# ElderBot.net
KiCad netlist of a schematic drawn in Altium Designer
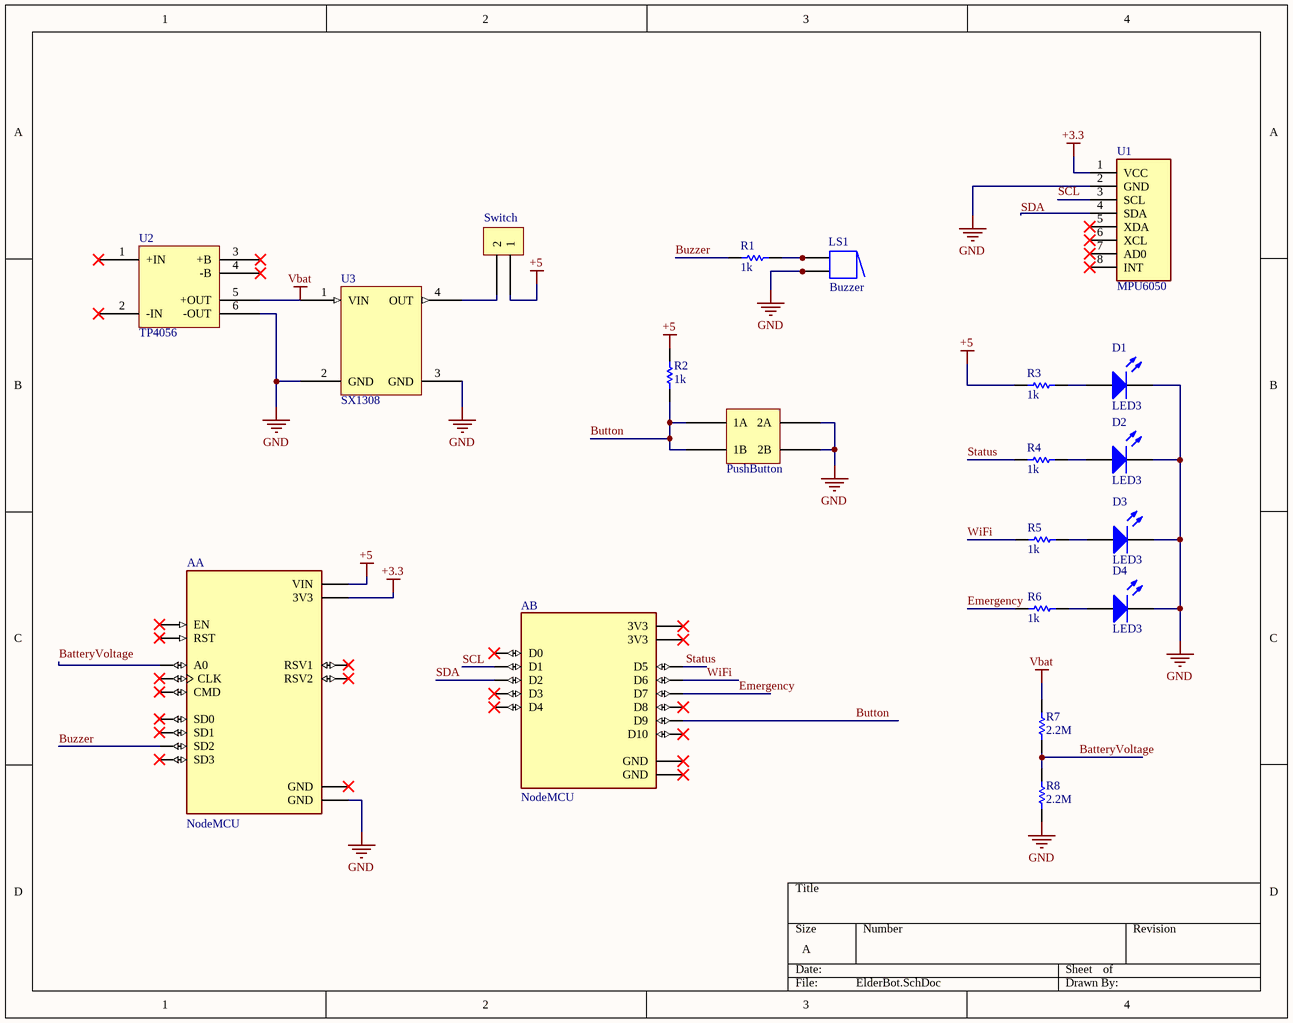
[diagram p0: ElderBot.SchDoc]

(export (version "E")
  (design (tool "Eeschema 10.0.6"))
  (components
    (comp (ref "A")
      (value "NodeMCU")
      (footprint "SEEED_113990105")
      (fields (field (name "MP") "NodeMCU v2") (field (name "MF") "Seeed Technology"))
      (libsource (lib "NodeMCU") (part "113990105"))
    )
    (comp (ref "D1")
      (value "LED3")
      (footprint "3.2X1.6X1.1")
      (description "Typical BLUE SiC LED")
      (fields (field (name "PUBLISHER") "Altium Limited"))
      (libsource (lib "Miscellaneous Devices") (part "LED3"))
    )
    (comp (ref "D2")
      (value "LED3")
      (footprint "3.2X1.6X1.1")
      (description "Typical BLUE SiC LED")
      (fields (field (name "PUBLISHER") "Altium Limited"))
      (libsource (lib "Miscellaneous Devices") (part "LED3"))
    )
    (comp (ref "D3")
      (value "LED3")
      (footprint "3.2X1.6X1.1")
      (description "Typical BLUE SiC LED")
      (fields (field (name "PUBLISHER") "Altium Limited"))
      (libsource (lib "Miscellaneous Devices") (part "LED3"))
    )
    (comp (ref "D4")
      (value "LED3")
      (footprint "3.2X1.6X1.1")
      (description "Typical BLUE SiC LED")
      (fields (field (name "PUBLISHER") "Altium Limited"))
      (libsource (lib "Miscellaneous Devices") (part "LED3"))
    )
    (comp (ref "LS1")
      (value "Buzzer")
      (footprint "Buzzer")
      (description "Magnetic Transducer Buzzer")
      (fields (field (name "PUBLISHER") "Altium Limited"))
      (libsource (lib "Miscellaneous Devices") (part "Buzzer"))
    )
    (comp (ref "R1")
      (value "1k")
      (footprint "RESC3116X70X50ML13T20")
      (description "Chip Resistor, 1 KOhm, +/- 1%, 0.25 W, -55 to 155 degC, 1206 (3216 Metric)")
      (fields (field (name "TOLERANCE") "1%") (field (name "POWER") "250mW"))
      (libsource (lib "University of Moratuwa") (part "RES-2"))
    )
    (comp (ref "R2")
      (value "1k")
      (footprint "RESC3116X70X50ML13T20")
      (description "Chip Resistor, 1 KOhm, +/- 1%, 0.25 W, -55 to 155 degC, 1206 (3216 Metric)")
      (fields (field (name "TOLERANCE") "1%") (field (name "POWER") "250mW"))
      (libsource (lib "University of Moratuwa") (part "RES-2"))
    )
    (comp (ref "R3")
      (value "1k")
      (footprint "RESC3116X70X50ML13T20")
      (description "Chip Resistor, 1 KOhm, +/- 1%, 0.25 W, -55 to 155 degC, 1206 (3216 Metric)")
      (fields (field (name "TOLERANCE") "1%") (field (name "POWER") "250mW"))
      (libsource (lib "University of Moratuwa") (part "RES-2"))
    )
    (comp (ref "R4")
      (value "1k")
      (footprint "RESC3116X70X50ML13T20")
      (description "Chip Resistor, 1 KOhm, +/- 1%, 0.25 W, -55 to 155 degC, 1206 (3216 Metric)")
      (fields (field (name "TOLERANCE") "1%") (field (name "POWER") "250mW"))
      (libsource (lib "University of Moratuwa") (part "RES-2"))
    )
    (comp (ref "R5")
      (value "1k")
      (footprint "RESC3116X70X50ML13T20")
      (description "Chip Resistor, 1 KOhm, +/- 1%, 0.25 W, -55 to 155 degC, 1206 (3216 Metric)")
      (fields (field (name "TOLERANCE") "1%") (field (name "POWER") "250mW"))
      (libsource (lib "University of Moratuwa") (part "RES-2"))
    )
    (comp (ref "R6")
      (value "1k")
      (footprint "RESC3116X70X50ML13T20")
      (description "Chip Resistor, 1 KOhm, +/- 1%, 0.25 W, -55 to 155 degC, 1206 (3216 Metric)")
      (fields (field (name "TOLERANCE") "1%") (field (name "POWER") "250mW"))
      (libsource (lib "University of Moratuwa") (part "RES-2"))
    )
    (comp (ref "R7")
      (value "2.2M")
      (footprint "RESC3116X70X50ML13T20")
      (description "Chip Resistor, 1 KOhm, +/- 1%, 0.25 W, -55 to 155 degC, 1206 (3216 Metric)")
      (fields (field (name "TOLERANCE") "1%") (field (name "POWER") "250mW"))
      (libsource (lib "University of Moratuwa") (part "RES-2"))
    )
    (comp (ref "R8")
      (value "2.2M")
      (footprint "RESC3116X70X50ML13T20")
      (description "Chip Resistor, 1 KOhm, +/- 1%, 0.25 W, -55 to 155 degC, 1206 (3216 Metric)")
      (fields (field (name "TOLERANCE") "1%") (field (name "POWER") "250mW"))
      (libsource (lib "University of Moratuwa") (part "RES-2"))
    )
    (comp (ref "S1") (value "Switch") (footprint "Switch") (libsource (lib "Misc") (part "Switch")))
    (comp (ref "S2")
      (value "PushButton")
      (footprint "PushButton")
      (libsource (lib "Misc") (part "PushButton"))
    )
    (comp (ref "U1") (value "MPU6050") (footprint "MPU6050") (libsource (lib "Misc") (part "MPU6050")))
    (comp (ref "U2") (value "TP4056") (footprint "TP4056") (libsource (lib "Misc") (part "TP4056")))
    (comp (ref "U3") (value "SX1308") (footprint "SX1308") (libsource (lib "Misc") (part "SX1308")))
  )
  (nets
    (net (code "1") (name "+3.3") (class "Default")
      (node (ref "A") (pin "J1_11") (pinfunction "3V3_J1_11") (pintype "power_in"))
      (node (ref "U1") (pin "1") (pinfunction "VCC_1") (pintype "power_in"))
    )
    (net (code "2") (name "+5") (class "Default")
      (node (ref "A") (pin "J1_15") (pinfunction "VIN_J1_15") (pintype "power_in"))
      (node (ref "R2") (pin "2") (pinfunction "2_2") (pintype "passive"))
      (node (ref "R3") (pin "1") (pinfunction "1_1") (pintype "passive"))
      (node (ref "S1") (pin "1") (pinfunction "1_1") (pintype "passive"))
    )
    (net (code "3") (name "/BatteryVoltage") (class "Default")
      (node (ref "A") (pin "J1_1") (pinfunction "A0_J1_1") (pintype "bidirectional"))
      (node (ref "R7") (pin "1") (pinfunction "1_1") (pintype "passive"))
      (node (ref "R8") (pin "2") (pinfunction "2_2") (pintype "passive"))
    )
    (net (code "4") (name "/Button") (class "Default")
      (node (ref "A") (pin "J2_12") (pinfunction "D9_J2_12") (pintype "bidirectional"))
      (node (ref "R2") (pin "1") (pinfunction "1_1") (pintype "passive"))
      (node (ref "S2") (pin "1A") (pinfunction "1A_1A") (pintype "passive"))
      (node (ref "S2") (pin "1B") (pinfunction "1B_1B") (pintype "passive"))
    )
    (net (code "5") (name "/Buzzer") (class "Default")
      (node (ref "A") (pin "J1_5") (pinfunction "SD2_J1_5") (pintype "bidirectional"))
      (node (ref "R1") (pin "1") (pinfunction "1_1") (pintype "passive"))
    )
    (net (code "6") (name "/Emergency") (class "Default")
      (node (ref "A") (pin "J2_10") (pinfunction "D7_J2_10") (pintype "bidirectional"))
      (node (ref "R6") (pin "1") (pinfunction "1_1") (pintype "passive"))
    )
    (net (code "7") (name "/SCL") (class "Default")
      (node (ref "A") (pin "J2_2") (pinfunction "D1_J2_2") (pintype "bidirectional"))
      (node (ref "U1") (pin "3") (pinfunction "SCL_3") (pintype "passive"))
    )
    (net (code "8") (name "/SDA") (class "Default")
      (node (ref "A") (pin "J2_3") (pinfunction "D2_J2_3") (pintype "bidirectional"))
      (node (ref "U1") (pin "4") (pinfunction "SDA_4") (pintype "passive"))
    )
    (net (code "9") (name "/Status") (class "Default")
      (node (ref "A") (pin "J2_8") (pinfunction "D5_J2_8") (pintype "bidirectional"))
      (node (ref "R4") (pin "1") (pinfunction "1_1") (pintype "passive"))
    )
    (net (code "10") (name "/WiFi") (class "Default")
      (node (ref "A") (pin "J2_9") (pinfunction "D6_J2_9") (pintype "bidirectional"))
      (node (ref "R5") (pin "1") (pinfunction "1_1") (pintype "passive"))
    )
    (net (code "11") (name "GND") (class "Default")
      (node (ref "A") (pin "J1_14") (pinfunction "GND_J1_14") (pintype "power_in"))
      (node (ref "D1") (pin "2") (pinfunction "K_2") (pintype "passive"))
      (node (ref "D2") (pin "2") (pinfunction "K_2") (pintype "passive"))
      (node (ref "D3") (pin "2") (pinfunction "K_2") (pintype "passive"))
      (node (ref "D4") (pin "2") (pinfunction "K_2") (pintype "passive"))
      (node (ref "LS1") (pin "2") (pinfunction "2_2") (pintype "passive"))
      (node (ref "LS1") (pin "2A") (pinfunction "2A_2A") (pintype "passive"))
      (node (ref "R8") (pin "1") (pinfunction "1_1") (pintype "passive"))
      (node (ref "S2") (pin "2A") (pinfunction "2A_2A") (pintype "passive"))
      (node (ref "S2") (pin "2B") (pinfunction "2B_2B") (pintype "passive"))
      (node (ref "U1") (pin "2") (pinfunction "GND_2") (pintype "power_in"))
      (node (ref "U2") (pin "6") (pinfunction "-OUT_6") (pintype "power_in"))
      (node (ref "U3") (pin "2") (pinfunction "GND_2") (pintype "power_in"))
      (node (ref "U3") (pin "3") (pinfunction "GND_3") (pintype "power_in"))
    )
    (net (code "12") (name "Net-(D1-A)") (class "Default")
      (node (ref "D1") (pin "1") (pinfunction "A_1") (pintype "passive"))
      (node (ref "R3") (pin "2") (pinfunction "2_2") (pintype "passive"))
    )
    (net (code "13") (name "Net-(D2-A)") (class "Default")
      (node (ref "D2") (pin "1") (pinfunction "A_1") (pintype "passive"))
      (node (ref "R4") (pin "2") (pinfunction "2_2") (pintype "passive"))
    )
    (net (code "14") (name "Net-(D3-A)") (class "Default")
      (node (ref "D3") (pin "1") (pinfunction "A_1") (pintype "passive"))
      (node (ref "R5") (pin "2") (pinfunction "2_2") (pintype "passive"))
    )
    (net (code "15") (name "Net-(D4-A)") (class "Default")
      (node (ref "D4") (pin "1") (pinfunction "A_1") (pintype "passive"))
      (node (ref "R6") (pin "2") (pinfunction "2_2") (pintype "passive"))
    )
    (net (code "16") (name "Net-(LS1-Pad1)") (class "Default")
      (node (ref "LS1") (pin "1") (pinfunction "1_1") (pintype "passive"))
      (node (ref "LS1") (pin "1A") (pinfunction "1A_1A") (pintype "passive"))
      (node (ref "R1") (pin "2") (pinfunction "2_2") (pintype "passive"))
    )
    (net (code "17") (name "Net-(U3-OUT)") (class "Default")
      (node (ref "S1") (pin "2") (pinfunction "2_2") (pintype "passive"))
      (node (ref "U3") (pin "4") (pinfunction "OUT_4") (pintype "output"))
    )
    (net (code "18") (name "Vbat") (class "Default")
      (node (ref "R7") (pin "2") (pinfunction "2_2") (pintype "passive"))
      (node (ref "U2") (pin "5") (pinfunction "+OUT_5") (pintype "power_in"))
      (node (ref "U3") (pin "1") (pinfunction "VIN_1") (pintype "input"))
    )
    (net (code "19") (name "unconnected-(AA-CLK-PadJ1_9)") (class "Default")
      (node (ref "A") (pin "J1_9") (pinfunction "CLK_J1_9") (pintype "bidirectional+no_connect"))
    )
    (net (code "20") (name "unconnected-(AA-CMD-PadJ1_7)") (class "Default")
      (node (ref "A") (pin "J1_7") (pinfunction "CMD_J1_7") (pintype "bidirectional+no_connect"))
    )
    (net (code "21") (name "unconnected-(AA-EN-PadJ1_12)") (class "Default")
      (node (ref "A") (pin "J1_12") (pinfunction "EN_J1_12") (pintype "input+no_connect"))
    )
    (net (code "22") (name "unconnected-(AA-GND-PadJ1_10)") (class "Default")
      (node (ref "A") (pin "J1_10") (pinfunction "GND_J1_10") (pintype "power_in+no_connect"))
    )
    (net (code "23") (name "unconnected-(AA-RST-PadJ1_13)") (class "Default")
      (node (ref "A") (pin "J1_13") (pinfunction "RST_J1_13") (pintype "input+no_connect"))
    )
    (net (code "24") (name "unconnected-(AA-RSV1-PadJ1_2)") (class "Default")
      (node (ref "A") (pin "J1_2") (pinfunction "RSV1_J1_2") (pintype "bidirectional+no_connect"))
    )
    (net (code "25") (name "unconnected-(AA-RSV2-PadJ1_3)") (class "Default")
      (node (ref "A") (pin "J1_3") (pinfunction "RSV2_J1_3") (pintype "bidirectional+no_connect"))
    )
    (net (code "26") (name "unconnected-(AA-SD0-PadJ1_8)") (class "Default")
      (node (ref "A") (pin "J1_8") (pinfunction "SD0_J1_8") (pintype "bidirectional+no_connect"))
    )
    (net (code "27") (name "unconnected-(AA-SD1-PadJ1_6)") (class "Default")
      (node (ref "A") (pin "J1_6") (pinfunction "SD1_J1_6") (pintype "bidirectional+no_connect"))
    )
    (net (code "28") (name "unconnected-(AA-SD3-PadJ1_4)") (class "Default")
      (node (ref "A") (pin "J1_4") (pinfunction "SD3_J1_4") (pintype "bidirectional+no_connect"))
    )
    (net (code "29") (name "unconnected-(AB-3V3-PadJ2_6)") (class "Default")
      (node (ref "A") (pin "J2_6") (pinfunction "3V3_J2_6") (pintype "power_in+no_connect"))
    )
    (net (code "30") (name "unconnected-(AB-3V3-PadJ2_15)") (class "Default")
      (node (ref "A") (pin "J2_15") (pinfunction "3V3_J2_15") (pintype "power_in+no_connect"))
    )
    (net (code "31") (name "unconnected-(AB-D0-PadJ2_1)") (class "Default")
      (node (ref "A") (pin "J2_1") (pinfunction "D0_J2_1") (pintype "bidirectional+no_connect"))
    )
    (net (code "32") (name "unconnected-(AB-D3-PadJ2_4)") (class "Default")
      (node (ref "A") (pin "J2_4") (pinfunction "D3_J2_4") (pintype "bidirectional+no_connect"))
    )
    (net (code "33") (name "unconnected-(AB-D4-PadJ2_5)") (class "Default")
      (node (ref "A") (pin "J2_5") (pinfunction "D4_J2_5") (pintype "bidirectional+no_connect"))
    )
    (net (code "34") (name "unconnected-(AB-D8-PadJ2_11)") (class "Default")
      (node (ref "A") (pin "J2_11") (pinfunction "D8_J2_11") (pintype "bidirectional+no_connect"))
    )
    (net (code "35") (name "unconnected-(AB-D10-PadJ2_13)") (class "Default")
      (node (ref "A") (pin "J2_13") (pinfunction "D10_J2_13") (pintype "bidirectional+no_connect"))
    )
    (net (code "36") (name "unconnected-(AB-GND-PadJ2_7)") (class "Default")
      (node (ref "A") (pin "J2_7") (pinfunction "GND_J2_7") (pintype "power_in+no_connect"))
    )
    (net (code "37") (name "unconnected-(AB-GND-PadJ2_14)") (class "Default")
      (node (ref "A") (pin "J2_14") (pinfunction "GND_J2_14") (pintype "power_in+no_connect"))
    )
    (net (code "38") (name "unconnected-(U1-AD0-Pad7)") (class "Default")
      (node (ref "U1") (pin "7") (pinfunction "AD0_7") (pintype "passive+no_connect"))
    )
    (net (code "39") (name "unconnected-(U1-INT-Pad8)") (class "Default")
      (node (ref "U1") (pin "8") (pinfunction "INT_8") (pintype "passive+no_connect"))
    )
    (net (code "40") (name "unconnected-(U1-XCL-Pad6)") (class "Default")
      (node (ref "U1") (pin "6") (pinfunction "XCL_6") (pintype "passive+no_connect"))
    )
    (net (code "41") (name "unconnected-(U1-XDA-Pad5)") (class "Default")
      (node (ref "U1") (pin "5") (pinfunction "XDA_5") (pintype "passive+no_connect"))
    )
    (net (code "42") (name "unconnected-(U2-+B-Pad3)") (class "Default")
      (node (ref "U2") (pin "3") (pinfunction "+B_3") (pintype "passive+no_connect"))
    )
    (net (code "43") (name "unconnected-(U2-+IN-Pad1)") (class "Default")
      (node (ref "U2") (pin "1") (pinfunction "+IN_1") (pintype "power_in+no_connect"))
    )
    (net (code "44") (name "unconnected-(U2--B-Pad4)") (class "Default")
      (node (ref "U2") (pin "4") (pinfunction "-B_4") (pintype "passive+no_connect"))
    )
    (net (code "45") (name "unconnected-(U2--IN-Pad2)") (class "Default")
      (node (ref "U2") (pin "2") (pinfunction "-IN_2") (pintype "power_in+no_connect"))
    )
  )
)
